# PIR.net
KiCad netlist of a schematic drawn in Altium Designer
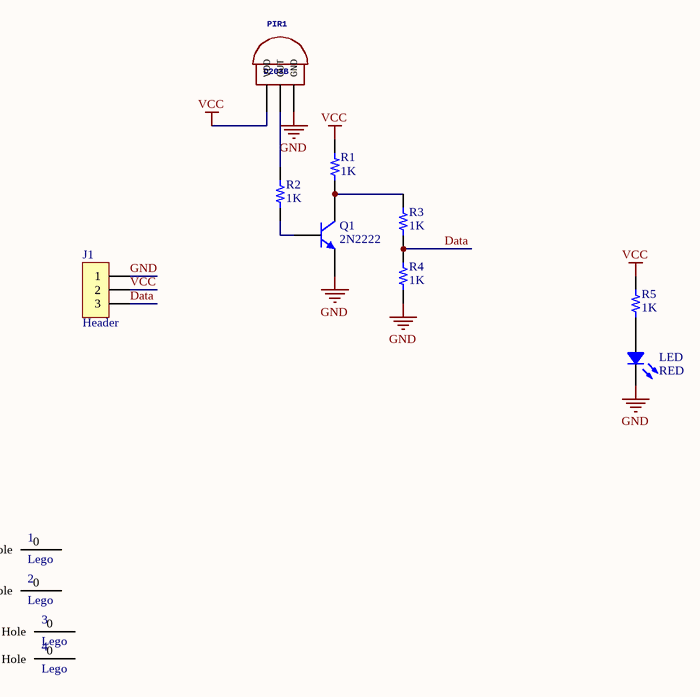
[diagram p0: PIR.SchDoc]

(export (version "E")
  (design (tool "Eeschema 10.0.6"))
  (components
    (comp (ref "1") (value "Lego") (footprint "Lego Hole") (libsource (lib "Connectors") (part "Lego")))
    (comp (ref "2") (value "Lego") (footprint "Lego Hole") (libsource (lib "Connectors") (part "Lego")))
    (comp (ref "3") (value "Lego") (footprint "Lego Hole") (libsource (lib "Connectors") (part "Lego")))
    (comp (ref "4") (value "Lego") (footprint "Lego Hole") (libsource (lib "Connectors") (part "Lego")))
    (comp (ref "J1")
      (value "Header")
      (footprint "MOLEX SDA-70553-3PIN")
      (libsource (lib "Connectors") (part "3 Pin"))
    )
    (comp (ref "LED")
      (value "RED")
      (footprint "LED 1206/3216 RED")
      (description "Chip LED")
      (libsource (lib "Cap_Res") (part "LED"))
    )
    (comp (ref "PIR1")
      (value "D203B")
      (footprint "D203B")
      (fields (field (name "LIBRARYNAME") "senba-pir-sensor"))
      (libsource (lib "Sensors") (part "D203B"))
    )
    (comp (ref "Q1")
      (value "2N2222")
      (footprint "SOT23")
      (description "NPN")
      (fields (field (name "E-MAIL") "picpars@gmail.com"))
      (libsource (lib "Other") (part "2N2222"))
    )
    (comp (ref "R1")
      (value "1K")
      (footprint "RES 1206/3216")
      (description "SMT Resistor")
      (libsource (lib "Cap_Res") (part "Resistor"))
    )
    (comp (ref "R2")
      (value "1K")
      (footprint "RES 1206/3216")
      (description "SMT Resistor")
      (libsource (lib "Cap_Res") (part "Resistor"))
    )
    (comp (ref "R3")
      (value "1K")
      (footprint "RES 1206/3216")
      (description "SMT Resistor")
      (libsource (lib "Cap_Res") (part "Resistor"))
    )
    (comp (ref "R4")
      (value "1K")
      (footprint "RES 1206/3216")
      (description "SMT Resistor")
      (libsource (lib "Cap_Res") (part "Resistor"))
    )
    (comp (ref "R5")
      (value "1K")
      (footprint "RES 1206/3216")
      (description "SMT Resistor")
      (libsource (lib "Cap_Res") (part "Resistor"))
    )
  )
  (nets
    (net (code "1") (name "/Data") (class "Default")
      (node (ref "J1") (pin "3") (pinfunction "3_3") (pintype "passive"))
      (node (ref "R3") (pin "2") (pinfunction "2_2") (pintype "passive"))
      (node (ref "R4") (pin "1") (pinfunction "1_1") (pintype "passive"))
    )
    (net (code "2") (name "GND") (class "Default")
      (node (ref "J1") (pin "1") (pinfunction "1_1") (pintype "passive"))
      (node (ref "LED") (pin "2") (pinfunction "2_2") (pintype "passive"))
      (node (ref "PIR1") (pin "3") (pinfunction "GND_3") (pintype "passive"))
      (node (ref "Q1") (pin "E") (pinfunction "E_E") (pintype "passive"))
      (node (ref "R4") (pin "2") (pinfunction "2_2") (pintype "passive"))
    )
    (net (code "3") (name "Net-(LED-Pad1)") (class "Default")
      (node (ref "LED") (pin "1") (pinfunction "1_1") (pintype "passive"))
      (node (ref "R5") (pin "1") (pinfunction "1_1") (pintype "passive"))
    )
    (net (code "4") (name "Net-(PIR1-OUT)") (class "Default")
      (node (ref "PIR1") (pin "2") (pinfunction "OUT_2") (pintype "passive"))
      (node (ref "R2") (pin "1") (pinfunction "1_1") (pintype "passive"))
    )
    (net (code "5") (name "Net-(Q1-PadB)") (class "Default")
      (node (ref "Q1") (pin "B") (pinfunction "B_B") (pintype "passive"))
      (node (ref "R2") (pin "2") (pinfunction "2_2") (pintype "passive"))
    )
    (net (code "6") (name "Net-(Q1-PadC)") (class "Default")
      (node (ref "Q1") (pin "C") (pinfunction "C_C") (pintype "passive"))
      (node (ref "R1") (pin "2") (pinfunction "2_2") (pintype "passive"))
      (node (ref "R3") (pin "1") (pinfunction "1_1") (pintype "passive"))
    )
    (net (code "7") (name "VCC") (class "Default")
      (node (ref "J1") (pin "2") (pinfunction "2_2") (pintype "passive"))
      (node (ref "PIR1") (pin "1") (pinfunction "VDD_1") (pintype "passive"))
      (node (ref "R1") (pin "1") (pinfunction "1_1") (pintype "passive"))
      (node (ref "R5") (pin "2") (pinfunction "2_2") (pintype "passive"))
    )
    (net (code "8") (name "unconnected-(1-Lego_Hole-Pad0)") (class "Default")
      (node (ref "1") (pin "0") (pinfunction "Lego_Hole_0") (pintype "passive"))
    )
    (net (code "9") (name "unconnected-(2-Lego_Hole-Pad0)") (class "Default")
      (node (ref "2") (pin "0") (pinfunction "Lego_Hole_0") (pintype "passive"))
    )
    (net (code "10") (name "unconnected-(3-Lego_Hole-Pad0)") (class "Default")
      (node (ref "3") (pin "0") (pinfunction "Lego_Hole_0") (pintype "passive"))
    )
    (net (code "11") (name "unconnected-(4-Lego_Hole-Pad0)") (class "Default")
      (node (ref "4") (pin "0") (pinfunction "Lego_Hole_0") (pintype "passive"))
    )
  )
)
